# HorsPCB.net
KiCad netlist of a schematic drawn in Altium Designer
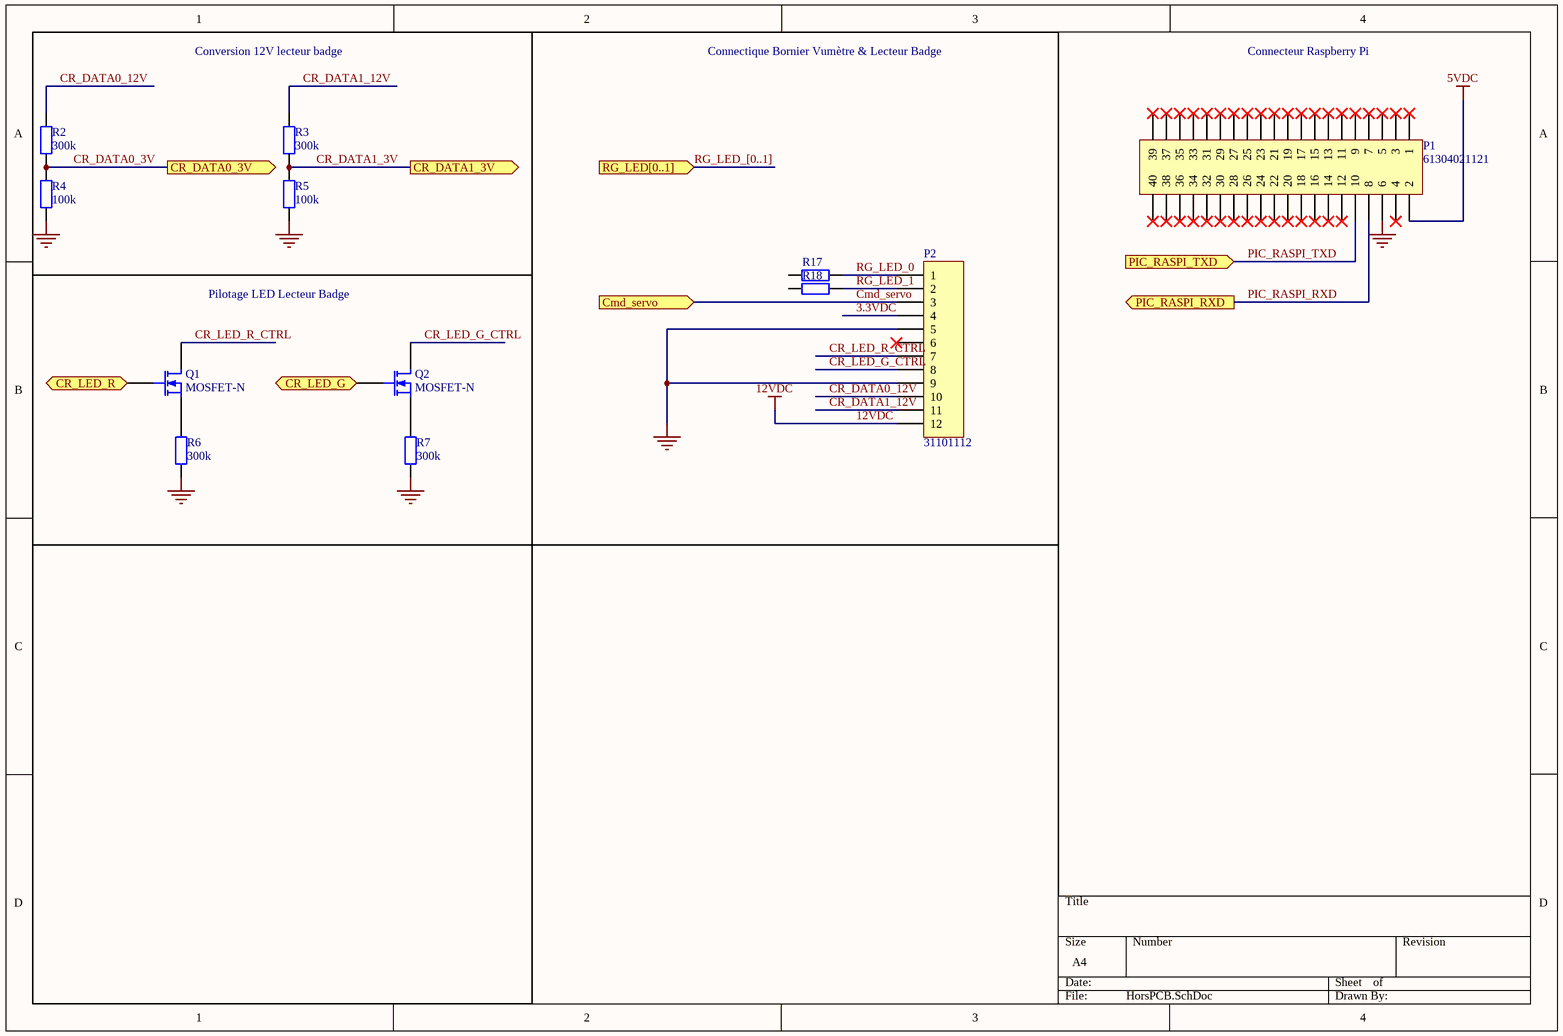
[diagram p0: HorsPCB.SchDoc]

(export (version "E")
  (design (tool "Eeschema 10.0.6"))
  (components
    (comp (ref "P1")
      (value "61304021121")
      (footprint "HDR2X20")
      (description "Header, 20-Pin, Dual row")
      (libsource (lib "Miscellaneous Connectors") (part "Header 20X2"))
    )
    (comp (ref "P2")
      (value "31101112")
      (footprint "HDR1X12")
      (description "Header, 12-Pin")
      (libsource (lib "Miscellaneous Connectors") (part "Header 12"))
    )
    (comp (ref "Q1")
      (value "MOSFET-N")
      (footprint "E3")
      (description "N-Channel MOSFET")
      (libsource (lib "Miscellaneous Devices") (part "MOSFET-N"))
    )
    (comp (ref "Q2")
      (value "MOSFET-N")
      (footprint "E3")
      (description "N-Channel MOSFET")
      (libsource (lib "Miscellaneous Devices") (part "MOSFET-N"))
    )
    (comp (ref "R2")
      (value "300k")
      (footprint "AXIAL-0.4")
      (description "Resistor")
      (libsource (lib "Miscellaneous Devices") (part "Res2"))
    )
    (comp (ref "R3")
      (value "300k")
      (footprint "AXIAL-0.4")
      (description "Resistor")
      (libsource (lib "Miscellaneous Devices") (part "Res2"))
    )
    (comp (ref "R4")
      (value "100k")
      (footprint "AXIAL-0.4")
      (description "Resistor")
      (libsource (lib "Miscellaneous Devices") (part "Res2"))
    )
    (comp (ref "R5")
      (value "100k")
      (footprint "AXIAL-0.4")
      (description "Resistor")
      (libsource (lib "Miscellaneous Devices") (part "Res2"))
    )
    (comp (ref "R6")
      (value "300k")
      (footprint "AXIAL-0.4")
      (description "Resistor")
      (libsource (lib "Miscellaneous Devices") (part "Res2"))
    )
    (comp (ref "R7")
      (value "300k")
      (footprint "AXIAL-0.4")
      (description "Resistor")
      (libsource (lib "Miscellaneous Devices") (part "Res2"))
    )
    (comp (ref "R17")
      (value "60.4")
      (footprint "AXIAL-0.4")
      (description "Resistor")
      (libsource (lib "") (part "Res2_1"))
    )
    (comp (ref "R18")
      (value "75")
      (footprint "AXIAL-0.4")
      (description "Resistor")
      (libsource (lib "") (part "Res2_1"))
    )
  )
  (nets
    (net (code "1") (name "/3.3VDC") (class "Default")
      (node (ref "P2") (pin "4") (pinfunction "4_4") (pintype "passive"))
    )
    (net (code "2") (name "/CR_DATA0_3V") (class "Default")
      (node (ref "R2") (pin "1") (pinfunction "1_1") (pintype "passive"))
      (node (ref "R4") (pin "2") (pinfunction "2_2") (pintype "passive"))
    )
    (net (code "3") (name "/CR_DATA0_12V") (class "Default")
      (node (ref "P2") (pin "10") (pinfunction "10_10") (pintype "passive"))
      (node (ref "R2") (pin "2") (pinfunction "2_2") (pintype "passive"))
    )
    (net (code "4") (name "/CR_DATA1_3V") (class "Default")
      (node (ref "R3") (pin "1") (pinfunction "1_1") (pintype "passive"))
      (node (ref "R5") (pin "2") (pinfunction "2_2") (pintype "passive"))
    )
    (net (code "5") (name "/CR_DATA1_12V") (class "Default")
      (node (ref "P2") (pin "11") (pinfunction "11_11") (pintype "passive"))
      (node (ref "R3") (pin "2") (pinfunction "2_2") (pintype "passive"))
    )
    (net (code "6") (name "/CR_LED_G") (class "Default")
      (node (ref "Q2") (pin "2") (pinfunction "G_2") (pintype "passive"))
    )
    (net (code "7") (name "/CR_LED_G_CTRL") (class "Default")
      (node (ref "P2") (pin "8") (pinfunction "8_8") (pintype "passive"))
      (node (ref "Q2") (pin "1") (pinfunction "D_1") (pintype "passive"))
    )
    (net (code "8") (name "/CR_LED_R") (class "Default")
      (node (ref "Q1") (pin "2") (pinfunction "G_2") (pintype "passive"))
    )
    (net (code "9") (name "/CR_LED_R_CTRL") (class "Default")
      (node (ref "P2") (pin "7") (pinfunction "7_7") (pintype "passive"))
      (node (ref "Q1") (pin "1") (pinfunction "D_1") (pintype "passive"))
    )
    (net (code "10") (name "/Cmd_servo") (class "Default")
      (node (ref "P2") (pin "3") (pinfunction "3_3") (pintype "passive"))
    )
    (net (code "11") (name "/PIC_RASPI_RXD") (class "Default")
      (node (ref "P1") (pin "8") (pinfunction "8_8") (pintype "passive"))
    )
    (net (code "12") (name "/PIC_RASPI_TXD") (class "Default")
      (node (ref "P1") (pin "10") (pinfunction "10_10") (pintype "passive"))
    )
    (net (code "13") (name "/RG_LED_0") (class "Default")
      (node (ref "P2") (pin "1") (pinfunction "1_1") (pintype "passive"))
      (node (ref "R17") (pin "2") (pinfunction "2_2") (pintype "passive"))
    )
    (net (code "14") (name "/RG_LED_1") (class "Default")
      (node (ref "P2") (pin "2") (pinfunction "2_2") (pintype "passive"))
      (node (ref "R18") (pin "2") (pinfunction "2_2") (pintype "passive"))
    )
    (net (code "16") (name "5VDC") (class "Default")
      (node (ref "P1") (pin "2") (pinfunction "2_2") (pintype "passive"))
    )
    (net (code "17") (name "12VDC") (class "Default")
      (node (ref "P2") (pin "12") (pinfunction "12_12") (pintype "passive"))
    )
    (net (code "18") (name "GND") (class "Default")
      (node (ref "P1") (pin "6") (pinfunction "6_6") (pintype "passive"))
      (node (ref "P2") (pin "5") (pinfunction "5_5") (pintype "passive"))
      (node (ref "P2") (pin "9") (pinfunction "9_9") (pintype "passive"))
      (node (ref "R4") (pin "1") (pinfunction "1_1") (pintype "passive"))
      (node (ref "R5") (pin "1") (pinfunction "1_1") (pintype "passive"))
      (node (ref "R6") (pin "1") (pinfunction "1_1") (pintype "passive"))
      (node (ref "R7") (pin "1") (pinfunction "1_1") (pintype "passive"))
    )
    (net (code "19") (name "Net-(Q1-S)") (class "Default")
      (node (ref "Q1") (pin "3") (pinfunction "S_3") (pintype "passive"))
      (node (ref "R6") (pin "2") (pinfunction "2_2") (pintype "passive"))
    )
    (net (code "20") (name "Net-(Q2-S)") (class "Default")
      (node (ref "Q2") (pin "3") (pinfunction "S_3") (pintype "passive"))
      (node (ref "R7") (pin "2") (pinfunction "2_2") (pintype "passive"))
    )
    (net (code "21") (name "unconnected-(P1-Pad1)") (class "Default")
      (node (ref "P1") (pin "1") (pinfunction "1_1") (pintype "passive+no_connect"))
    )
    (net (code "22") (name "unconnected-(P1-Pad3)") (class "Default")
      (node (ref "P1") (pin "3") (pinfunction "3_3") (pintype "passive+no_connect"))
    )
    (net (code "23") (name "unconnected-(P1-Pad4)") (class "Default")
      (node (ref "P1") (pin "4") (pinfunction "4_4") (pintype "passive+no_connect"))
    )
    (net (code "24") (name "unconnected-(P1-Pad5)") (class "Default")
      (node (ref "P1") (pin "5") (pinfunction "5_5") (pintype "passive+no_connect"))
    )
    (net (code "25") (name "unconnected-(P1-Pad7)") (class "Default")
      (node (ref "P1") (pin "7") (pinfunction "7_7") (pintype "passive+no_connect"))
    )
    (net (code "26") (name "unconnected-(P1-Pad9)") (class "Default")
      (node (ref "P1") (pin "9") (pinfunction "9_9") (pintype "passive+no_connect"))
    )
    (net (code "27") (name "unconnected-(P1-Pad11)") (class "Default")
      (node (ref "P1") (pin "11") (pinfunction "11_11") (pintype "passive+no_connect"))
    )
    (net (code "28") (name "unconnected-(P1-Pad12)") (class "Default")
      (node (ref "P1") (pin "12") (pinfunction "12_12") (pintype "passive+no_connect"))
    )
    (net (code "29") (name "unconnected-(P1-Pad13)") (class "Default")
      (node (ref "P1") (pin "13") (pinfunction "13_13") (pintype "passive+no_connect"))
    )
    (net (code "30") (name "unconnected-(P1-Pad14)") (class "Default")
      (node (ref "P1") (pin "14") (pinfunction "14_14") (pintype "passive+no_connect"))
    )
    (net (code "31") (name "unconnected-(P1-Pad15)") (class "Default")
      (node (ref "P1") (pin "15") (pinfunction "15_15") (pintype "passive+no_connect"))
    )
    (net (code "32") (name "unconnected-(P1-Pad16)") (class "Default")
      (node (ref "P1") (pin "16") (pinfunction "16_16") (pintype "passive+no_connect"))
    )
    (net (code "33") (name "unconnected-(P1-Pad17)") (class "Default")
      (node (ref "P1") (pin "17") (pinfunction "17_17") (pintype "passive+no_connect"))
    )
    (net (code "34") (name "unconnected-(P1-Pad18)") (class "Default")
      (node (ref "P1") (pin "18") (pinfunction "18_18") (pintype "passive+no_connect"))
    )
    (net (code "35") (name "unconnected-(P1-Pad19)") (class "Default")
      (node (ref "P1") (pin "19") (pinfunction "19_19") (pintype "passive+no_connect"))
    )
    (net (code "36") (name "unconnected-(P1-Pad20)") (class "Default")
      (node (ref "P1") (pin "20") (pinfunction "20_20") (pintype "passive+no_connect"))
    )
    (net (code "37") (name "unconnected-(P1-Pad21)") (class "Default")
      (node (ref "P1") (pin "21") (pinfunction "21_21") (pintype "passive+no_connect"))
    )
    (net (code "38") (name "unconnected-(P1-Pad22)") (class "Default")
      (node (ref "P1") (pin "22") (pinfunction "22_22") (pintype "passive+no_connect"))
    )
    (net (code "39") (name "unconnected-(P1-Pad23)") (class "Default")
      (node (ref "P1") (pin "23") (pinfunction "23_23") (pintype "passive+no_connect"))
    )
    (net (code "40") (name "unconnected-(P1-Pad24)") (class "Default")
      (node (ref "P1") (pin "24") (pinfunction "24_24") (pintype "passive+no_connect"))
    )
    (net (code "41") (name "unconnected-(P1-Pad25)") (class "Default")
      (node (ref "P1") (pin "25") (pinfunction "25_25") (pintype "passive+no_connect"))
    )
    (net (code "42") (name "unconnected-(P1-Pad26)") (class "Default")
      (node (ref "P1") (pin "26") (pinfunction "26_26") (pintype "passive+no_connect"))
    )
    (net (code "43") (name "unconnected-(P1-Pad27)") (class "Default")
      (node (ref "P1") (pin "27") (pinfunction "27_27") (pintype "passive+no_connect"))
    )
    (net (code "44") (name "unconnected-(P1-Pad28)") (class "Default")
      (node (ref "P1") (pin "28") (pinfunction "28_28") (pintype "passive+no_connect"))
    )
    (net (code "45") (name "unconnected-(P1-Pad29)") (class "Default")
      (node (ref "P1") (pin "29") (pinfunction "29_29") (pintype "passive+no_connect"))
    )
    (net (code "46") (name "unconnected-(P1-Pad30)") (class "Default")
      (node (ref "P1") (pin "30") (pinfunction "30_30") (pintype "passive+no_connect"))
    )
    (net (code "47") (name "unconnected-(P1-Pad31)") (class "Default")
      (node (ref "P1") (pin "31") (pinfunction "31_31") (pintype "passive+no_connect"))
    )
    (net (code "48") (name "unconnected-(P1-Pad32)") (class "Default")
      (node (ref "P1") (pin "32") (pinfunction "32_32") (pintype "passive+no_connect"))
    )
    (net (code "49") (name "unconnected-(P1-Pad33)") (class "Default")
      (node (ref "P1") (pin "33") (pinfunction "33_33") (pintype "passive+no_connect"))
    )
    (net (code "50") (name "unconnected-(P1-Pad34)") (class "Default")
      (node (ref "P1") (pin "34") (pinfunction "34_34") (pintype "passive+no_connect"))
    )
    (net (code "51") (name "unconnected-(P1-Pad35)") (class "Default")
      (node (ref "P1") (pin "35") (pinfunction "35_35") (pintype "passive+no_connect"))
    )
    (net (code "52") (name "unconnected-(P1-Pad36)") (class "Default")
      (node (ref "P1") (pin "36") (pinfunction "36_36") (pintype "passive+no_connect"))
    )
    (net (code "53") (name "unconnected-(P1-Pad37)") (class "Default")
      (node (ref "P1") (pin "37") (pinfunction "37_37") (pintype "passive+no_connect"))
    )
    (net (code "54") (name "unconnected-(P1-Pad38)") (class "Default")
      (node (ref "P1") (pin "38") (pinfunction "38_38") (pintype "passive+no_connect"))
    )
    (net (code "55") (name "unconnected-(P1-Pad39)") (class "Default")
      (node (ref "P1") (pin "39") (pinfunction "39_39") (pintype "passive+no_connect"))
    )
    (net (code "56") (name "unconnected-(P1-Pad40)") (class "Default")
      (node (ref "P1") (pin "40") (pinfunction "40_40") (pintype "passive+no_connect"))
    )
    (net (code "57") (name "unconnected-(P2-Pad6)") (class "Default")
      (node (ref "P2") (pin "6") (pinfunction "6_6") (pintype "passive+no_connect"))
    )
    (net (code "58") (name "unconnected-(R17-Pad1)") (class "Default")
      (node (ref "R17") (pin "1") (pinfunction "1_1") (pintype "passive"))
    )
    (net (code "59") (name "unconnected-(R18-Pad1)") (class "Default")
      (node (ref "R18") (pin "1") (pinfunction "1_1") (pintype "passive"))
    )
  )
)
